# EspressoCircuitry.net
KiCad netlist of a schematic drawn in EAGLE
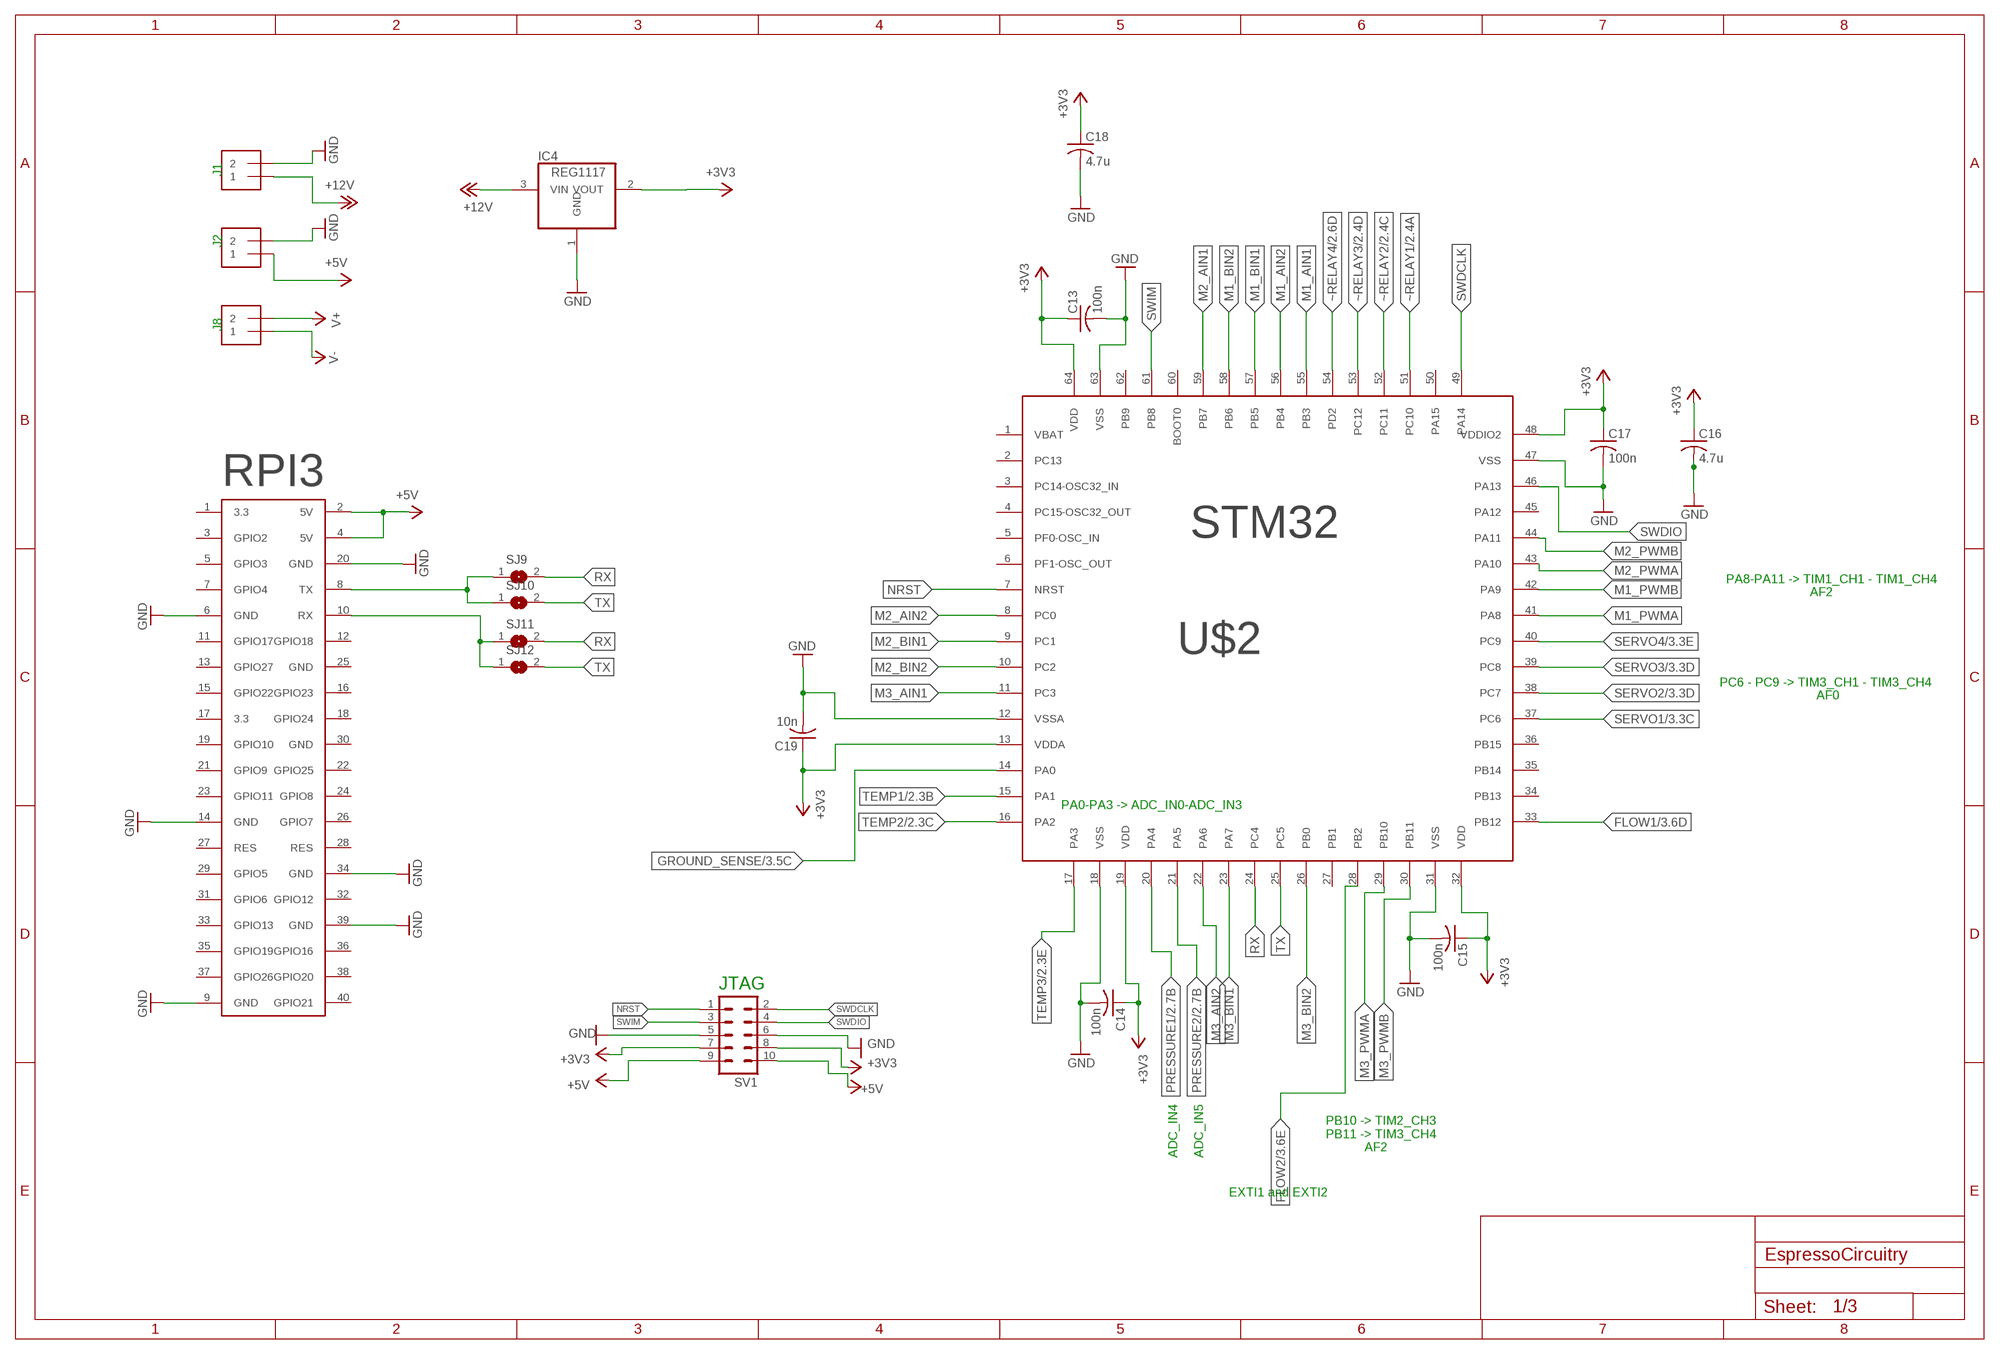
[diagram p0: schematic, sheet 1]
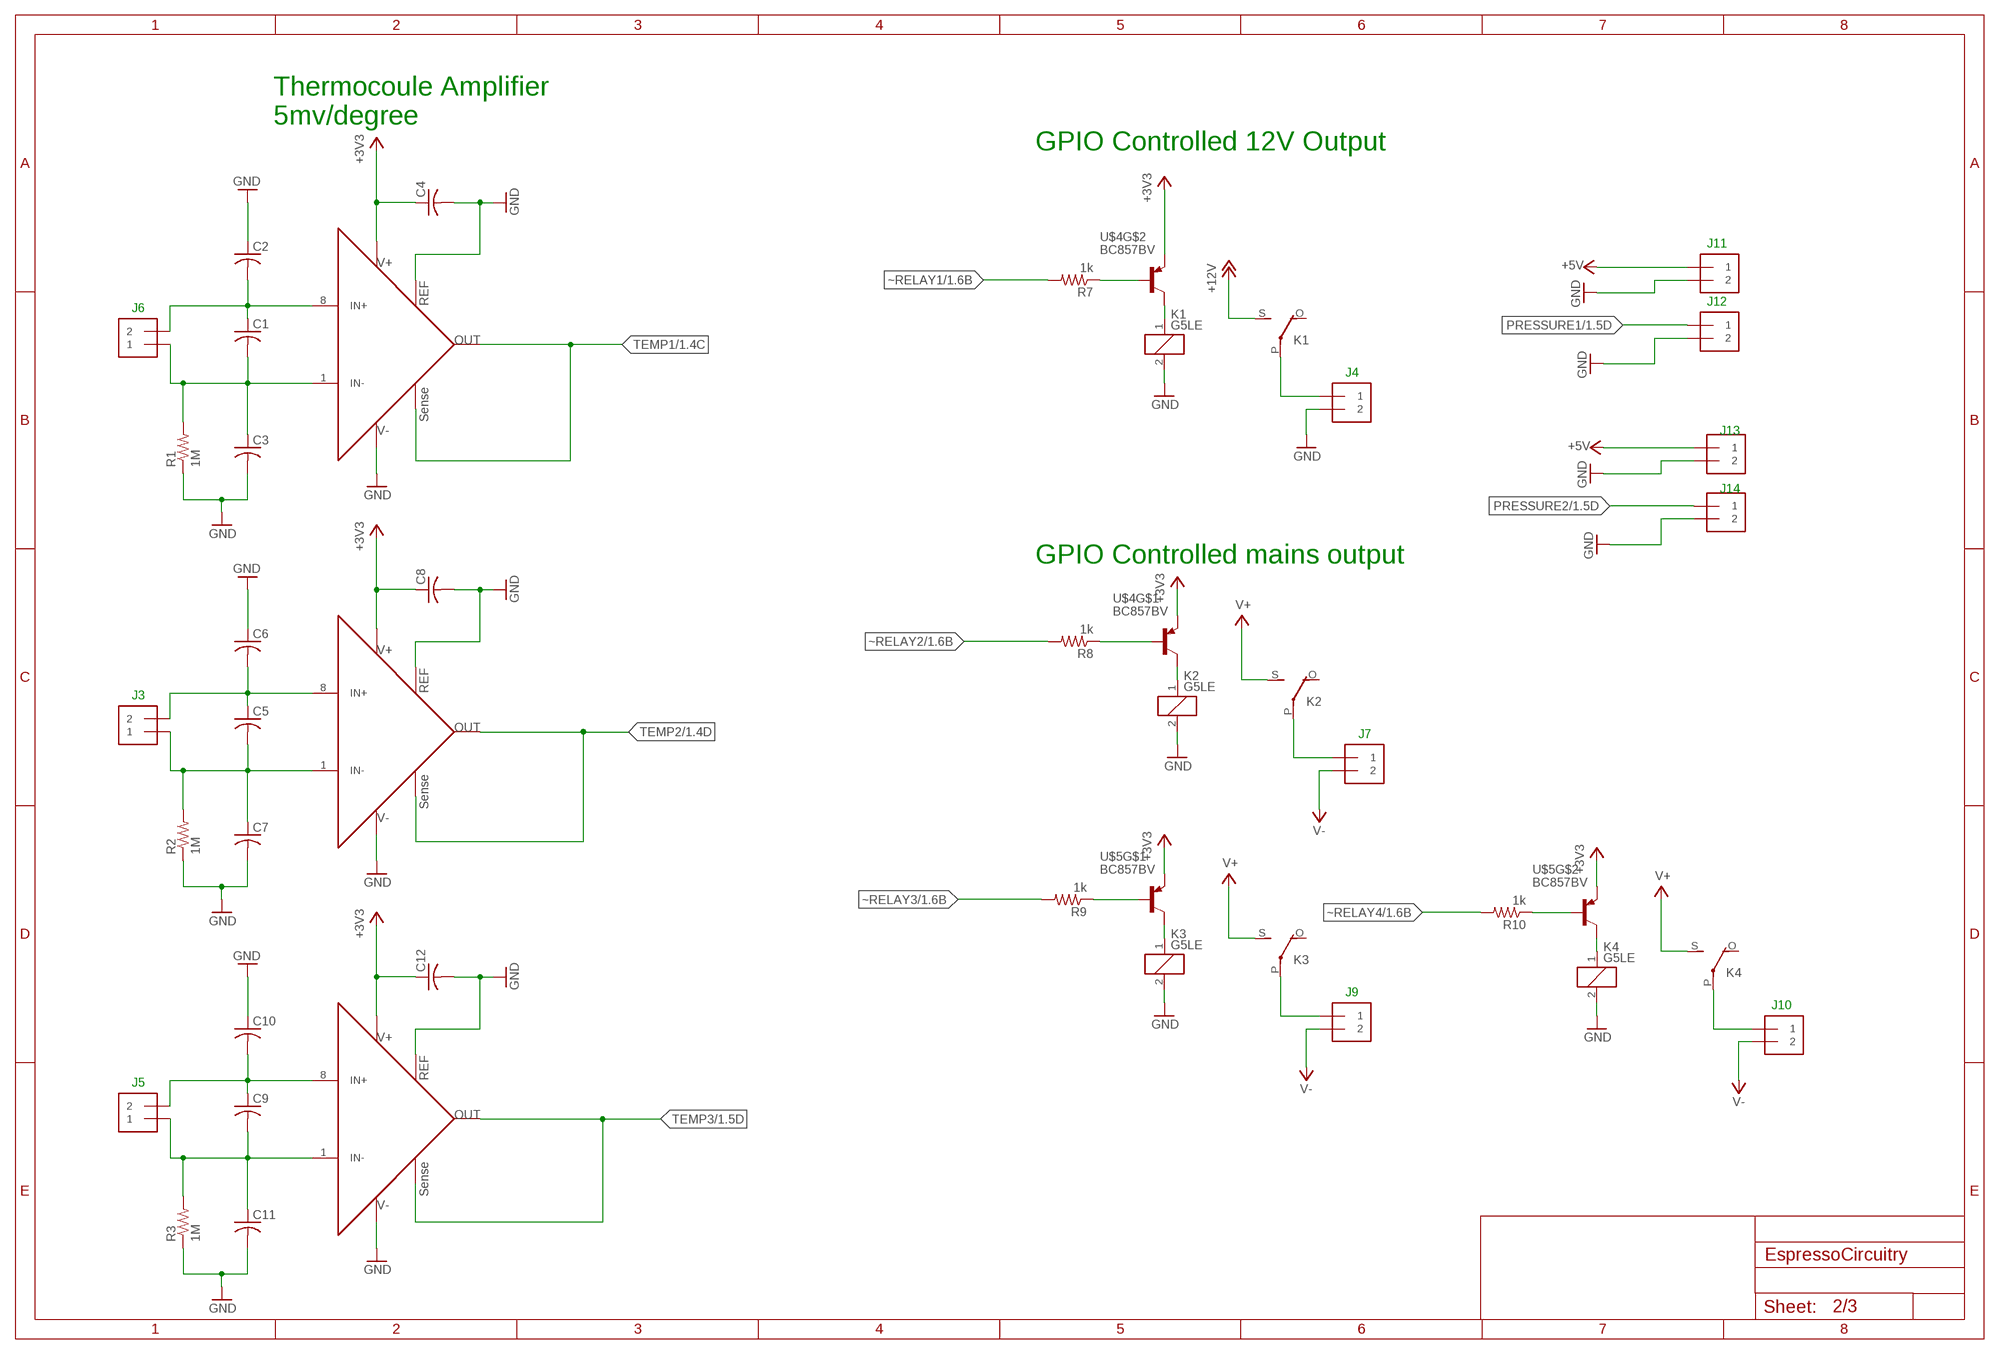
[diagram p1: schematic, sheet 2]
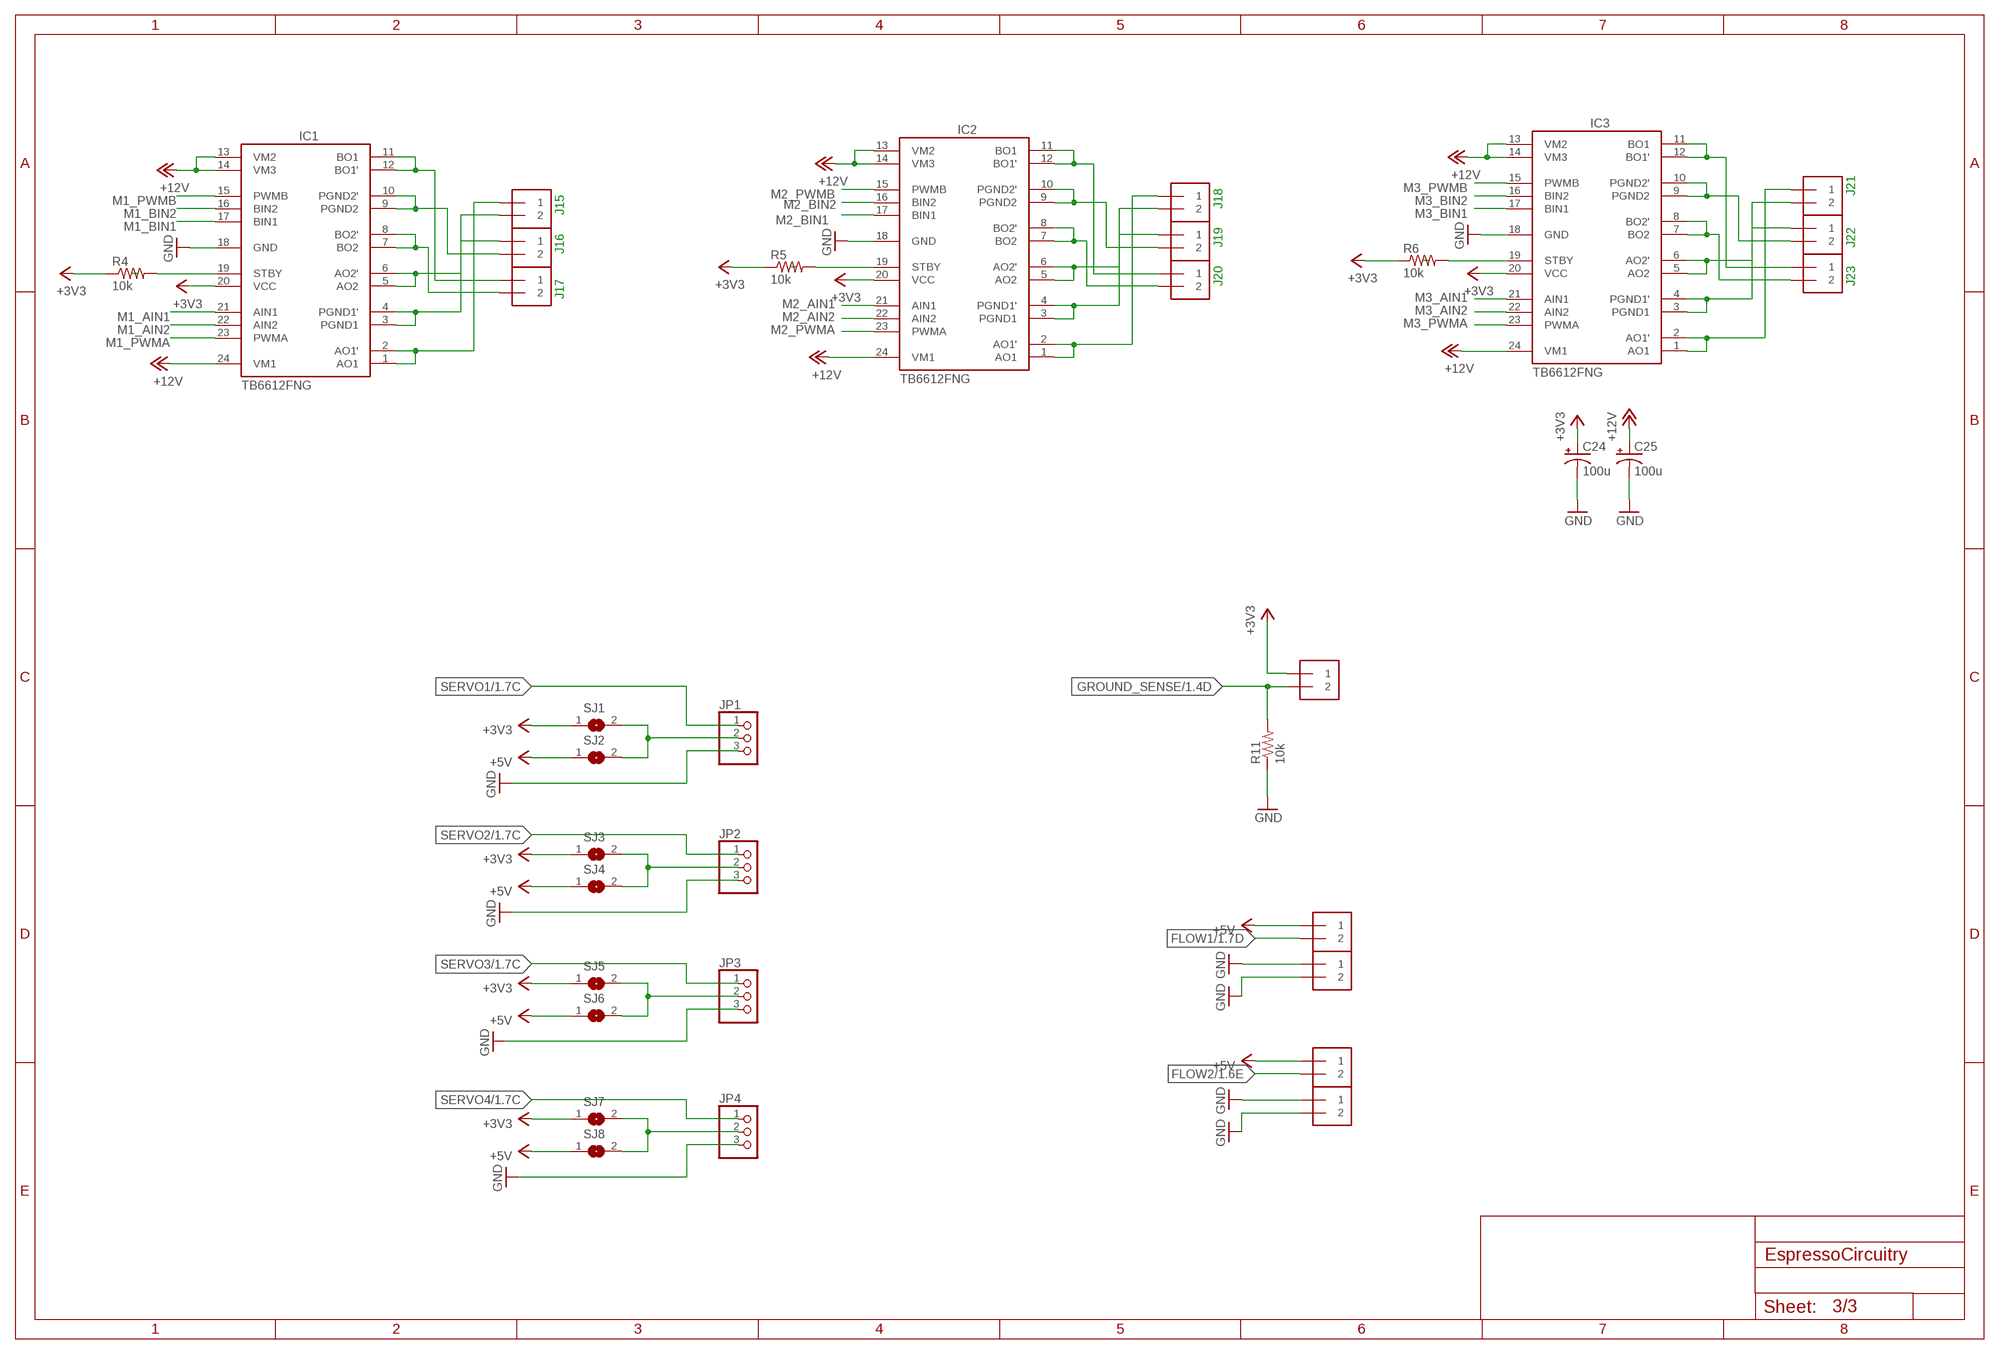
[diagram p2: schematic, sheet 3]

(export (version "E")
  (design (tool "Eeschema 10.0.6"))
  (components
    (comp (ref "C1")
      (value "C-USC0603")
      (footprint "eagle-import:C0603")
      (libsource (lib "eagle-import") (part "C-USC0603"))
    )
    (comp (ref "C2")
      (value "C-USC0603")
      (footprint "eagle-import:C0603")
      (libsource (lib "eagle-import") (part "C-USC0603"))
    )
    (comp (ref "C3")
      (value "C-USC0603")
      (footprint "eagle-import:C0603")
      (libsource (lib "eagle-import") (part "C-USC0603"))
    )
    (comp (ref "C4")
      (value "C-USC0603")
      (footprint "eagle-import:C0603")
      (libsource (lib "eagle-import") (part "C-USC0603"))
    )
    (comp (ref "C5")
      (value "C-USC0603")
      (footprint "eagle-import:C0603")
      (libsource (lib "eagle-import") (part "C-USC0603"))
    )
    (comp (ref "C6")
      (value "C-USC0603")
      (footprint "eagle-import:C0603")
      (libsource (lib "eagle-import") (part "C-USC0603"))
    )
    (comp (ref "C7")
      (value "C-USC0603")
      (footprint "eagle-import:C0603")
      (libsource (lib "eagle-import") (part "C-USC0603"))
    )
    (comp (ref "C8")
      (value "C-USC0603")
      (footprint "eagle-import:C0603")
      (libsource (lib "eagle-import") (part "C-USC0603"))
    )
    (comp (ref "C9")
      (value "C-USC0603")
      (footprint "eagle-import:C0603")
      (libsource (lib "eagle-import") (part "C-USC0603"))
    )
    (comp (ref "C10")
      (value "C-USC0603")
      (footprint "eagle-import:C0603")
      (libsource (lib "eagle-import") (part "C-USC0603"))
    )
    (comp (ref "C11")
      (value "C-USC0603")
      (footprint "eagle-import:C0603")
      (libsource (lib "eagle-import") (part "C-USC0603"))
    )
    (comp (ref "C12")
      (value "C-USC0603")
      (footprint "eagle-import:C0603")
      (libsource (lib "eagle-import") (part "C-USC0603"))
    )
    (comp (ref "J3")
      (value "1X2-3.5MM")
      (footprint "eagle-import:1X2-3.5MM")
      (libsource (lib "eagle-import") (part "1X2-3.5MM"))
    )
    (comp (ref "J4")
      (value "1X2-3.5MM")
      (footprint "eagle-import:1X2-3.5MM")
      (libsource (lib "eagle-import") (part "1X2-3.5MM"))
    )
    (comp (ref "J5")
      (value "1X2-3.5MM")
      (footprint "eagle-import:1X2-3.5MM")
      (libsource (lib "eagle-import") (part "1X2-3.5MM"))
    )
    (comp (ref "J6")
      (value "1X2-3.5MM")
      (footprint "eagle-import:1X2-3.5MM")
      (libsource (lib "eagle-import") (part "1X2-3.5MM"))
    )
    (comp (ref "J7")
      (value "1X2-3.5MM")
      (footprint "eagle-import:1X2-3.5MM")
      (libsource (lib "eagle-import") (part "1X2-3.5MM"))
    )
    (comp (ref "J9")
      (value "1X2-3.5MM")
      (footprint "eagle-import:1X2-3.5MM")
      (libsource (lib "eagle-import") (part "1X2-3.5MM"))
    )
    (comp (ref "J10")
      (value "1X2-3.5MM")
      (footprint "eagle-import:1X2-3.5MM")
      (libsource (lib "eagle-import") (part "1X2-3.5MM"))
    )
    (comp (ref "J11")
      (value "1X2-3.5MM")
      (footprint "eagle-import:1X2-3.5MM")
      (libsource (lib "eagle-import") (part "1X2-3.5MM"))
    )
    (comp (ref "J12")
      (value "1X2-3.5MM")
      (footprint "eagle-import:1X2-3.5MM")
      (libsource (lib "eagle-import") (part "1X2-3.5MM"))
    )
    (comp (ref "J13")
      (value "1X2-3.5MM")
      (footprint "eagle-import:1X2-3.5MM")
      (libsource (lib "eagle-import") (part "1X2-3.5MM"))
    )
    (comp (ref "J14")
      (value "1X2-3.5MM")
      (footprint "eagle-import:1X2-3.5MM")
      (libsource (lib "eagle-import") (part "1X2-3.5MM"))
    )
    (comp (ref "K1")
      (value "G5LE")
      (footprint "eagle-import:G5LE")
      (libsource (lib "eagle-import") (part "G5LE"))
    )
    (comp (ref "K2")
      (value "G5LE")
      (footprint "eagle-import:G5LE")
      (libsource (lib "eagle-import") (part "G5LE"))
    )
    (comp (ref "K3")
      (value "G5LE")
      (footprint "eagle-import:G5LE")
      (libsource (lib "eagle-import") (part "G5LE"))
    )
    (comp (ref "K4")
      (value "G5LE")
      (footprint "eagle-import:G5LE")
      (libsource (lib "eagle-import") (part "G5LE"))
    )
    (comp (ref "R1")
      (value "1M")
      (footprint "eagle-import:R0603")
      (libsource (lib "eagle-import") (part "R-US_R0603"))
    )
    (comp (ref "R2")
      (value "1M")
      (footprint "eagle-import:R0603")
      (libsource (lib "eagle-import") (part "R-US_R0603"))
    )
    (comp (ref "R3")
      (value "1M")
      (footprint "eagle-import:R0603")
      (libsource (lib "eagle-import") (part "R-US_R0603"))
    )
    (comp (ref "R7")
      (value "1k")
      (footprint "eagle-import:R0603")
      (libsource (lib "eagle-import") (part "R-US_R0603"))
    )
    (comp (ref "R8")
      (value "1k")
      (footprint "eagle-import:R0603")
      (libsource (lib "eagle-import") (part "R-US_R0603"))
    )
    (comp (ref "R9")
      (value "1k")
      (footprint "eagle-import:R0603")
      (libsource (lib "eagle-import") (part "R-US_R0603"))
    )
    (comp (ref "R10")
      (value "1k")
      (footprint "eagle-import:R0603")
      (libsource (lib "eagle-import") (part "R-US_R0603"))
    )
    (comp (ref "U$3")
      (value "AD8494")
      (footprint "eagle-import:TSSOP8")
      (libsource (lib "eagle-import") (part "AD8494"))
    )
    (comp (ref "U$4")
      (value "BC857BV")
      (footprint "eagle-import:SOT-563")
      (libsource (lib "eagle-import") (part "BC857BV"))
    )
    (comp (ref "U$5")
      (value "BC857BV")
      (footprint "eagle-import:SOT-563")
      (libsource (lib "eagle-import") (part "BC857BV"))
    )
    (comp (ref "U$6")
      (value "AD8494")
      (footprint "eagle-import:TSSOP8")
      (libsource (lib "eagle-import") (part "AD8494"))
    )
    (comp (ref "U$7")
      (value "AD8494")
      (footprint "eagle-import:TSSOP8")
      (libsource (lib "eagle-import") (part "AD8494"))
    )
    (comp (ref "C13")
      (value "100n")
      (footprint "eagle-import:C0603")
      (libsource (lib "eagle-import") (part "C-USC0603"))
    )
    (comp (ref "C14")
      (value "100n")
      (footprint "eagle-import:C0603")
      (libsource (lib "eagle-import") (part "C-USC0603"))
    )
    (comp (ref "C15")
      (value "100n")
      (footprint "eagle-import:C0603")
      (libsource (lib "eagle-import") (part "C-USC0603"))
    )
    (comp (ref "C16")
      (value "4.7u")
      (footprint "eagle-import:C0603")
      (libsource (lib "eagle-import") (part "C-USC0603"))
    )
    (comp (ref "C17")
      (value "100n")
      (footprint "eagle-import:C0603")
      (libsource (lib "eagle-import") (part "C-USC0603"))
    )
    (comp (ref "C18")
      (value "4.7u")
      (footprint "eagle-import:C0603")
      (libsource (lib "eagle-import") (part "C-USC0603"))
    )
    (comp (ref "C19")
      (value "10n")
      (footprint "eagle-import:C0603")
      (libsource (lib "eagle-import") (part "C-USC0603"))
    )
    (comp (ref "IC4")
      (value "REG1117")
      (footprint "eagle-import:SOT223")
      (libsource (lib "eagle-import") (part "REG1117"))
    )
    (comp (ref "J1")
      (value "1X2-3.5MM")
      (footprint "eagle-import:1X2-3.5MM")
      (libsource (lib "eagle-import") (part "1X2-3.5MM"))
    )
    (comp (ref "J2")
      (value "1X2-3.5MM")
      (footprint "eagle-import:1X2-3.5MM")
      (libsource (lib "eagle-import") (part "1X2-3.5MM"))
    )
    (comp (ref "J8")
      (value "1X2-3.5MM")
      (footprint "eagle-import:1X2-3.5MM")
      (libsource (lib "eagle-import") (part "1X2-3.5MM"))
    )
    (comp (ref "SJ9") (value "SJ") (footprint "eagle-import:SJ") (libsource (lib "eagle-import") (part "SJ")))
    (comp (ref "SJ10")
      (value "SJ")
      (footprint "eagle-import:SJ")
      (libsource (lib "eagle-import") (part "SJ"))
    )
    (comp (ref "SJ11")
      (value "SJ")
      (footprint "eagle-import:SJ")
      (libsource (lib "eagle-import") (part "SJ"))
    )
    (comp (ref "SJ12")
      (value "SJ")
      (footprint "eagle-import:SJ")
      (libsource (lib "eagle-import") (part "SJ"))
    )
    (comp (ref "SV1")
      (value "MA05-2")
      (footprint "eagle-import:MA05-2")
      (libsource (lib "eagle-import") (part "MA05-2"))
    )
    (comp (ref "U$1")
      (value "RPI")
      (footprint "eagle-import:FE20-2")
      (libsource (lib "eagle-import") (part "RPI"))
    )
    (comp (ref "U$2")
      (value "STM32F072RBT6LGFP64")
      (footprint "eagle-import:PLQFP64-1")
      (libsource (lib "eagle-import") (part "STM32F072RBT6LGFP64"))
    )
    (comp (ref "C24")
      (value "100u")
      (footprint "eagle-import:E2,5-5")
      (libsource (lib "eagle-import") (part "CPOL-USE2.5-5"))
    )
    (comp (ref "C25")
      (value "100u")
      (footprint "eagle-import:E2,5-5")
      (libsource (lib "eagle-import") (part "CPOL-USE2.5-5"))
    )
    (comp (ref "IC1")
      (value "TB6612FNG")
      (footprint "eagle-import:SSOP24")
      (libsource (lib "eagle-import") (part "TB6612FNG"))
    )
    (comp (ref "IC2")
      (value "TB6612FNG")
      (footprint "eagle-import:SSOP24")
      (libsource (lib "eagle-import") (part "TB6612FNG"))
    )
    (comp (ref "IC3")
      (value "TB6612FNG")
      (footprint "eagle-import:SSOP24")
      (libsource (lib "eagle-import") (part "TB6612FNG"))
    )
    (comp (ref "J15")
      (value "1X2-3.5MM")
      (footprint "eagle-import:1X2-3.5MM")
      (libsource (lib "eagle-import") (part "1X2-3.5MM"))
    )
    (comp (ref "J16")
      (value "1X2-3.5MM")
      (footprint "eagle-import:1X2-3.5MM")
      (libsource (lib "eagle-import") (part "1X2-3.5MM"))
    )
    (comp (ref "J17")
      (value "1X2-3.5MM")
      (footprint "eagle-import:1X2-3.5MM")
      (libsource (lib "eagle-import") (part "1X2-3.5MM"))
    )
    (comp (ref "J18")
      (value "1X2-3.5MM")
      (footprint "eagle-import:1X2-3.5MM")
      (libsource (lib "eagle-import") (part "1X2-3.5MM"))
    )
    (comp (ref "J19")
      (value "1X2-3.5MM")
      (footprint "eagle-import:1X2-3.5MM")
      (libsource (lib "eagle-import") (part "1X2-3.5MM"))
    )
    (comp (ref "J20")
      (value "1X2-3.5MM")
      (footprint "eagle-import:1X2-3.5MM")
      (libsource (lib "eagle-import") (part "1X2-3.5MM"))
    )
    (comp (ref "J21")
      (value "1X2-3.5MM")
      (footprint "eagle-import:1X2-3.5MM")
      (libsource (lib "eagle-import") (part "1X2-3.5MM"))
    )
    (comp (ref "J22")
      (value "1X2-3.5MM")
      (footprint "eagle-import:1X2-3.5MM")
      (libsource (lib "eagle-import") (part "1X2-3.5MM"))
    )
    (comp (ref "J23")
      (value "1X2-3.5MM")
      (footprint "eagle-import:1X2-3.5MM")
      (libsource (lib "eagle-import") (part "1X2-3.5MM"))
    )
    (comp (ref "J24")
      (value "1X2-3.5MM")
      (footprint "eagle-import:1X2-3.5MM")
      (libsource (lib "eagle-import") (part "1X2-3.5MM"))
    )
    (comp (ref "J25")
      (value "1X2-3.5MM")
      (footprint "eagle-import:1X2-3.5MM")
      (libsource (lib "eagle-import") (part "1X2-3.5MM"))
    )
    (comp (ref "J26")
      (value "1X2-3.5MM")
      (footprint "eagle-import:1X2-3.5MM")
      (libsource (lib "eagle-import") (part "1X2-3.5MM"))
    )
    (comp (ref "J27")
      (value "1X2-3.5MM")
      (footprint "eagle-import:1X2-3.5MM")
      (libsource (lib "eagle-import") (part "1X2-3.5MM"))
    )
    (comp (ref "J28")
      (value "1X2-3.5MM")
      (footprint "eagle-import:1X2-3.5MM")
      (libsource (lib "eagle-import") (part "1X2-3.5MM"))
    )
    (comp (ref "JP1")
      (value "PINHD-1X3")
      (footprint "eagle-import:1X03")
      (libsource (lib "eagle-import") (part "PINHD-1X3"))
    )
    (comp (ref "JP2")
      (value "PINHD-1X3")
      (footprint "eagle-import:1X03")
      (libsource (lib "eagle-import") (part "PINHD-1X3"))
    )
    (comp (ref "JP3")
      (value "PINHD-1X3")
      (footprint "eagle-import:1X03")
      (libsource (lib "eagle-import") (part "PINHD-1X3"))
    )
    (comp (ref "JP4")
      (value "PINHD-1X3")
      (footprint "eagle-import:1X03")
      (libsource (lib "eagle-import") (part "PINHD-1X3"))
    )
    (comp (ref "R4")
      (value "10k")
      (footprint "eagle-import:R0603")
      (libsource (lib "eagle-import") (part "R-US_R0603"))
    )
    (comp (ref "R5")
      (value "10k")
      (footprint "eagle-import:R0603")
      (libsource (lib "eagle-import") (part "R-US_R0603"))
    )
    (comp (ref "R6")
      (value "10k")
      (footprint "eagle-import:R0603")
      (libsource (lib "eagle-import") (part "R-US_R0603"))
    )
    (comp (ref "R11")
      (value "10k")
      (footprint "eagle-import:R0603")
      (libsource (lib "eagle-import") (part "R-US_R0603"))
    )
    (comp (ref "SJ1") (value "SJ") (footprint "eagle-import:SJ") (libsource (lib "eagle-import") (part "SJ")))
    (comp (ref "SJ2") (value "SJ") (footprint "eagle-import:SJ") (libsource (lib "eagle-import") (part "SJ")))
    (comp (ref "SJ3") (value "SJ") (footprint "eagle-import:SJ") (libsource (lib "eagle-import") (part "SJ")))
    (comp (ref "SJ4") (value "SJ") (footprint "eagle-import:SJ") (libsource (lib "eagle-import") (part "SJ")))
    (comp (ref "SJ5") (value "SJ") (footprint "eagle-import:SJ") (libsource (lib "eagle-import") (part "SJ")))
    (comp (ref "SJ6") (value "SJ") (footprint "eagle-import:SJ") (libsource (lib "eagle-import") (part "SJ")))
    (comp (ref "SJ7") (value "SJ") (footprint "eagle-import:SJ") (libsource (lib "eagle-import") (part "SJ")))
    (comp (ref "SJ8") (value "SJ") (footprint "eagle-import:SJ") (libsource (lib "eagle-import") (part "SJ")))
  )
  (nets
    (net (code "1") (name "+3V3") (class "Default")
      (node (ref "C12") (pin "1") (pinfunction "1_1") (pintype "passive"))
      (node (ref "C13") (pin "1") (pinfunction "1_1") (pintype "passive"))
      (node (ref "C14") (pin "1") (pinfunction "1_1") (pintype "passive"))
      (node (ref "C15") (pin "1") (pinfunction "1_1") (pintype "passive"))
      (node (ref "C16") (pin "1") (pinfunction "1_1") (pintype "passive"))
      (node (ref "C17") (pin "1") (pinfunction "1_1") (pintype "passive"))
      (node (ref "C18") (pin "1") (pinfunction "1_1") (pintype "passive"))
      (node (ref "C19") (pin "1") (pinfunction "1_1") (pintype "passive"))
      (node (ref "C24") (pin "+") (pinfunction "+_+") (pintype "passive"))
      (node (ref "C4") (pin "1") (pinfunction "1_1") (pintype "passive"))
      (node (ref "C8") (pin "1") (pinfunction "1_1") (pintype "passive"))
      (node (ref "IC1") (pin "20") (pinfunction "VCC_20") (pintype "power_in"))
      (node (ref "IC2") (pin "20") (pinfunction "VCC_20") (pintype "power_in"))
      (node (ref "IC3") (pin "20") (pinfunction "VCC_20") (pintype "power_in"))
      (node (ref "IC4") (pin "2") (pinfunction "VOUT_2") (pintype "output"))
      (node (ref "J24") (pin "1") (pinfunction "1_1") (pintype "passive"))
      (node (ref "R4") (pin "1") (pinfunction "1_1") (pintype "passive"))
      (node (ref "R5") (pin "1") (pinfunction "1_1") (pintype "passive"))
      (node (ref "R6") (pin "1") (pinfunction "1_1") (pintype "passive"))
      (node (ref "SJ1") (pin "1") (pinfunction "1_1") (pintype "passive"))
      (node (ref "SJ3") (pin "1") (pinfunction "1_1") (pintype "passive"))
      (node (ref "SJ5") (pin "1") (pinfunction "1_1") (pintype "passive"))
      (node (ref "SJ7") (pin "1") (pinfunction "1_1") (pintype "passive"))
      (node (ref "SV1") (pin "7") (pinfunction "7_7") (pintype "passive"))
      (node (ref "SV1") (pin "8") (pinfunction "8_8") (pintype "passive"))
      (node (ref "U$2") (pin "13") (pinfunction "VDDA_13") (pintype "bidirectional"))
      (node (ref "U$2") (pin "19") (pinfunction "VDD_19") (pintype "bidirectional"))
      (node (ref "U$2") (pin "32") (pinfunction "VDD_32") (pintype "bidirectional"))
      (node (ref "U$2") (pin "48") (pinfunction "VDDIO2_48") (pintype "bidirectional"))
      (node (ref "U$2") (pin "64") (pinfunction "VDD_64") (pintype "bidirectional"))
      (node (ref "U$3") (pin "7") (pinfunction "V+_7") (pintype "bidirectional"))
      (node (ref "U$4") (pin "P$3") (pinfunction "E_P$3") (pintype "passive"))
      (node (ref "U$4") (pin "P$6") (pinfunction "E_P$6") (pintype "passive"))
      (node (ref "U$5") (pin "P$3") (pinfunction "E_P$3") (pintype "passive"))
      (node (ref "U$5") (pin "P$6") (pinfunction "E_P$6") (pintype "passive"))
      (node (ref "U$6") (pin "7") (pinfunction "V+_7") (pintype "bidirectional"))
      (node (ref "U$7") (pin "7") (pinfunction "V+_7") (pintype "bidirectional"))
    )
    (net (code "2") (name "+5V") (class "Default")
      (node (ref "J11") (pin "1") (pinfunction "1_1") (pintype "passive"))
      (node (ref "J13") (pin "1") (pinfunction "1_1") (pintype "passive"))
      (node (ref "J2") (pin "1") (pinfunction "1_1") (pintype "passive"))
      (node (ref "J25") (pin "1") (pinfunction "1_1") (pintype "passive"))
      (node (ref "J27") (pin "1") (pinfunction "1_1") (pintype "passive"))
      (node (ref "SJ2") (pin "1") (pinfunction "1_1") (pintype "passive"))
      (node (ref "SJ4") (pin "1") (pinfunction "1_1") (pintype "passive"))
      (node (ref "SJ6") (pin "1") (pinfunction "1_1") (pintype "passive"))
      (node (ref "SJ8") (pin "1") (pinfunction "1_1") (pintype "passive"))
      (node (ref "SV1") (pin "10") (pinfunction "10_10") (pintype "passive"))
      (node (ref "SV1") (pin "9") (pinfunction "9_9") (pintype "passive"))
      (node (ref "U$1") (pin "2") (pinfunction "5V_2") (pintype "bidirectional"))
      (node (ref "U$1") (pin "4") (pinfunction "5V_4") (pintype "bidirectional"))
    )
    (net (code "3") (name "+12V") (class "Default")
      (node (ref "C25") (pin "+") (pinfunction "+_+") (pintype "passive"))
      (node (ref "IC1") (pin "13") (pinfunction "VM2_13") (pintype "power_in"))
      (node (ref "IC1") (pin "14") (pinfunction "VM3_14") (pintype "power_in"))
      (node (ref "IC1") (pin "24") (pinfunction "VM1_24") (pintype "power_in"))
      (node (ref "IC2") (pin "13") (pinfunction "VM2_13") (pintype "power_in"))
      (node (ref "IC2") (pin "14") (pinfunction "VM3_14") (pintype "power_in"))
      (node (ref "IC2") (pin "24") (pinfunction "VM1_24") (pintype "power_in"))
      (node (ref "IC3") (pin "13") (pinfunction "VM2_13") (pintype "power_in"))
      (node (ref "IC3") (pin "14") (pinfunction "VM3_14") (pintype "power_in"))
      (node (ref "IC3") (pin "24") (pinfunction "VM1_24") (pintype "power_in"))
      (node (ref "IC4") (pin "3") (pinfunction "VIN_3") (pintype "input"))
      (node (ref "J1") (pin "1") (pinfunction "1_1") (pintype "passive"))
      (node (ref "K1") (pin "S") (pinfunction "S_S") (pintype "passive"))
    )
    (net (code "4") (name "FLOW1") (class "Default")
      (node (ref "J25") (pin "2") (pinfunction "2_2") (pintype "passive"))
      (node (ref "U$2") (pin "33") (pinfunction "PB12_33") (pintype "bidirectional"))
    )
    (net (code "5") (name "FLOW2") (class "Default")
      (node (ref "J27") (pin "2") (pinfunction "2_2") (pintype "passive"))
      (node (ref "U$2") (pin "28") (pinfunction "PB2_28") (pintype "bidirectional"))
    )
    (net (code "6") (name "GND") (class "Default")
      (node (ref "C10") (pin "1") (pinfunction "1_1") (pintype "passive"))
      (node (ref "C11") (pin "2") (pinfunction "2_2") (pintype "passive"))
      (node (ref "C12") (pin "2") (pinfunction "2_2") (pintype "passive"))
      (node (ref "C13") (pin "2") (pinfunction "2_2") (pintype "passive"))
      (node (ref "C14") (pin "2") (pinfunction "2_2") (pintype "passive"))
      (node (ref "C15") (pin "2") (pinfunction "2_2") (pintype "passive"))
      (node (ref "C16") (pin "2") (pinfunction "2_2") (pintype "passive"))
      (node (ref "C17") (pin "2") (pinfunction "2_2") (pintype "passive"))
      (node (ref "C18") (pin "2") (pinfunction "2_2") (pintype "passive"))
      (node (ref "C19") (pin "2") (pinfunction "2_2") (pintype "passive"))
      (node (ref "C2") (pin "1") (pinfunction "1_1") (pintype "passive"))
      (node (ref "C24") (pin "-") (pinfunction "-_-") (pintype "passive"))
      (node (ref "C25") (pin "-") (pinfunction "-_-") (pintype "passive"))
      (node (ref "C3") (pin "2") (pinfunction "2_2") (pintype "passive"))
      (node (ref "C4") (pin "2") (pinfunction "2_2") (pintype "passive"))
      (node (ref "C6") (pin "1") (pinfunction "1_1") (pintype "passive"))
      (node (ref "C7") (pin "2") (pinfunction "2_2") (pintype "passive"))
      (node (ref "C8") (pin "2") (pinfunction "2_2") (pintype "passive"))
      (node (ref "IC1") (pin "18") (pinfunction "GND_18") (pintype "power_in"))
      (node (ref "IC2") (pin "18") (pinfunction "GND_18") (pintype "power_in"))
      (node (ref "IC3") (pin "18") (pinfunction "GND_18") (pintype "power_in"))
      (node (ref "IC4") (pin "1") (pinfunction "GND_1") (pintype "power_in"))
      (node (ref "J1") (pin "2") (pinfunction "2_2") (pintype "passive"))
      (node (ref "J11") (pin "2") (pinfunction "2_2") (pintype "passive"))
      (node (ref "J12") (pin "2") (pinfunction "2_2") (pintype "passive"))
      (node (ref "J13") (pin "2") (pinfunction "2_2") (pintype "passive"))
      (node (ref "J14") (pin "2") (pinfunction "2_2") (pintype "passive"))
      (node (ref "J2") (pin "2") (pinfunction "2_2") (pintype "passive"))
      (node (ref "J26") (pin "1") (pinfunction "1_1") (pintype "passive"))
      (node (ref "J26") (pin "2") (pinfunction "2_2") (pintype "passive"))
      (node (ref "J28") (pin "1") (pinfunction "1_1") (pintype "passive"))
      (node (ref "J28") (pin "2") (pinfunction "2_2") (pintype "passive"))
      (node (ref "J4") (pin "2") (pinfunction "2_2") (pintype "passive"))
      (node (ref "JP1") (pin "3") (pinfunction "3_3") (pintype "passive"))
      (node (ref "JP2") (pin "3") (pinfunction "3_3") (pintype "passive"))
      (node (ref "JP3") (pin "3") (pinfunction "3_3") (pintype "passive"))
      (node (ref "JP4") (pin "3") (pinfunction "3_3") (pintype "passive"))
      (node (ref "K1") (pin "2") (pinfunction "2_2") (pintype "passive"))
      (node (ref "K2") (pin "2") (pinfunction "2_2") (pintype "passive"))
      (node (ref "K3") (pin "2") (pinfunction "2_2") (pintype "passive"))
      (node (ref "K4") (pin "2") (pinfunction "2_2") (pintype "passive"))
      (node (ref "R1") (pin "1") (pinfunction "1_1") (pintype "passive"))
      (node (ref "R11") (pin "1") (pinfunction "1_1") (pintype "passive"))
      (node (ref "R2") (pin "1") (pinfunction "1_1") (pintype "passive"))
      (node (ref "R3") (pin "1") (pinfunction "1_1") (pintype "passive"))
      (node (ref "SV1") (pin "5") (pinfunction "5_5") (pintype "passive"))
      (node (ref "SV1") (pin "6") (pinfunction "6_6") (pintype "passive"))
      (node (ref "U$1") (pin "14") (pinfunction "GND_14") (pintype "bidirectional"))
      (node (ref "U$1") (pin "20") (pinfunction "GND_20") (pintype "bidirectional"))
      (node (ref "U$1") (pin "34") (pinfunction "GND_34") (pintype "bidirectional"))
      (node (ref "U$1") (pin "39") (pinfunction "GND_39") (pintype "bidirectional"))
      (node (ref "U$1") (pin "6") (pinfunction "GND_6") (pintype "bidirectional"))
      (node (ref "U$1") (pin "9") (pinfunction "GND_9") (pintype "bidirectional"))
      (node (ref "U$2") (pin "12") (pinfunction "VSSA_12") (pintype "bidirectional"))
      (node (ref "U$2") (pin "18") (pinfunction "VSS_18") (pintype "bidirectional"))
      (node (ref "U$2") (pin "31") (pinfunction "VSS_31") (pintype "bidirectional"))
      (node (ref "U$2") (pin "47") (pinfunction "VSS_47") (pintype "bidirectional"))
      (node (ref "U$2") (pin "63") (pinfunction "VSS_63") (pintype "bidirectional"))
      (node (ref "U$3") (pin "2") (pinfunction "REF_2") (pintype "bidirectional"))
      (node (ref "U$3") (pin "3") (pinfunction "V-_3") (pintype "bidirectional"))
      (node (ref "U$6") (pin "2") (pinfunction "REF_2") (pintype "bidirectional"))
      (node (ref "U$6") (pin "3") (pinfunction "V-_3") (pintype "bidirectional"))
      (node (ref "U$7") (pin "2") (pinfunction "REF_2") (pintype "bidirectional"))
      (node (ref "U$7") (pin "3") (pinfunction "V-_3") (pintype "bidirectional"))
    )
    (net (code "7") (name "GROUND_SENSE") (class "Default")
      (node (ref "J24") (pin "2") (pinfunction "2_2") (pintype "passive"))
      (node (ref "R11") (pin "2") (pinfunction "2_2") (pintype "passive"))
      (node (ref "U$2") (pin "14") (pinfunction "PA0_14") (pintype "bidirectional"))
    )
    (net (code "8") (name "M1_AIN1") (class "Default")
      (node (ref "IC1") (pin "21") (pinfunction "AIN1_21") (pintype "input"))
      (node (ref "U$2") (pin "55") (pinfunction "PB3_55") (pintype "bidirectional"))
    )
    (net (code "9") (name "M1_AIN2") (class "Default")
      (node (ref "IC1") (pin "22") (pinfunction "AIN2_22") (pintype "input"))
      (node (ref "U$2") (pin "56") (pinfunction "PB4_56") (pintype "bidirectional"))
    )
    (net (code "10") (name "M1_BIN1") (class "Default")
      (node (ref "IC1") (pin "17") (pinfunction "BIN1_17") (pintype "input"))
      (node (ref "U$2") (pin "57") (pinfunction "PB5_57") (pintype "bidirectional"))
    )
    (net (code "11") (name "M1_BIN2") (class "Default")
      (node (ref "IC1") (pin "16") (pinfunction "BIN2_16") (pintype "input"))
      (node (ref "U$2") (pin "58") (pinfunction "PB6_58") (pintype "bidirectional"))
    )
    (net (code "12") (name "M1_PWMA") (class "Default")
      (node (ref "IC1") (pin "23") (pinfunction "PWMA_23") (pintype "input"))
      (node (ref "U$2") (pin "41") (pinfunction "PA8_41") (pintype "bidirectional"))
    )
    (net (code "13") (name "M1_PWMB") (class "Default")
      (node (ref "IC1") (pin "15") (pinfunction "PWMB_15") (pintype "input"))
      (node (ref "U$2") (pin "42") (pinfunction "PA9_42") (pintype "bidirectional"))
    )
    (net (code "14") (name "M2_AIN1") (class "Default")
      (node (ref "IC2") (pin "21") (pinfunction "AIN1_21") (pintype "input"))
      (node (ref "U$2") (pin "59") (pinfunction "PB7_59") (pintype "bidirectional"))
    )
    (net (code "15") (name "M2_AIN2") (class "Default")
      (node (ref "IC2") (pin "22") (pinfunction "AIN2_22") (pintype "input"))
      (node (ref "U$2") (pin "8") (pinfunction "PC0_8") (pintype "bidirectional"))
    )
    (net (code "16") (name "M2_BIN1") (class "Default")
      (node (ref "IC2") (pin "17") (pinfunction "BIN1_17") (pintype "input"))
      (node (ref "U$2") (pin "9") (pinfunction "PC1_9") (pintype "bidirectional"))
    )
    (net (code "17") (name "M2_BIN2") (class "Default")
      (node (ref "IC2") (pin "16") (pinfunction "BIN2_16") (pintype "input"))
      (node (ref "U$2") (pin "10") (pinfunction "PC2_10") (pintype "bidirectional"))
    )
    (net (code "18") (name "M2_PWMA") (class "Default")
      (node (ref "IC2") (pin "23") (pinfunction "PWMA_23") (pintype "input"))
      (node (ref "U$2") (pin "43") (pinfunction "PA10_43") (pintype "bidirectional"))
    )
    (net (code "19") (name "M2_PWMB") (class "Default")
      (node (ref "IC2") (pin "15") (pinfunction "PWMB_15") (pintype "input"))
      (node (ref "U$2") (pin "44") (pinfunction "PA11_44") (pintype "bidirectional"))
    )
    (net (code "20") (name "M3_AIN1") (class "Default")
      (node (ref "IC3") (pin "21") (pinfunction "AIN1_21") (pintype "input"))
      (node (ref "U$2") (pin "11") (pinfunction "PC3_11") (pintype "bidirectional"))
    )
    (net (code "21") (name "M3_AIN2") (class "Default")
      (node (ref "IC3") (pin "22") (pinfunction "AIN2_22") (pintype "input"))
      (node (ref "U$2") (pin "22") (pinfunction "PA6_22") (pintype "bidirectional"))
    )
    (net (code "22") (name "M3_BIN1") (class "Default")
      (node (ref "IC3") (pin "17") (pinfunction "BIN1_17") (pintype "input"))
      (node (ref "U$2") (pin "23") (pinfunction "PA7_23") (pintype "bidirectional"))
    )
    (net (code "23") (name "M3_BIN2") (class "Default")
      (node (ref "IC3") (pin "16") (pinfunction "BIN2_16") (pintype "input"))
      (node (ref "U$2") (pin "26") (pinfunction "PB0_26") (pintype "bidirectional"))
    )
    (net (code "24") (name "M3_PWMA") (class "Default")
      (node (ref "IC3") (pin "23") (pinfunction "PWMA_23") (pintype "input"))
      (node (ref "U$2") (pin "29") (pinfunction "PB10_29") (pintype "bidirectional"))
    )
    (net (code "25") (name "M3_PWMB") (class "Default")
      (node (ref "IC3") (pin "15") (pinfunction "PWMB_15") (pintype "input"))
      (node (ref "U$2") (pin "30") (pinfunction "PB11_30") (pintype "bidirectional"))
    )
    (net (code "26") (name "NRST") (class "Default")
      (node (ref "SV1") (pin "1") (pinfunction "1_1") (pintype "passive"))
      (node (ref "U$2") (pin "7") (pinfunction "NRST_7") (pintype "bidirectional"))
    )
    (net (code "27") (name "Net-(IC1-AO1')") (class "Default")
      (node (ref "IC1") (pin "1") (pinfunction "AO1_1") (pintype "output"))
      (node (ref "IC1") (pin "2") (pinfunction "AO1'_2") (pintype "output"))
      (node (ref "J15") (pin "1") (pinfunction "1_1") (pintype "passive"))
    )
    (net (code "28") (name "Net-(IC1-AO2')") (class "Default")
      (node (ref "IC1") (pin "5") (pinfunction "AO2_5") (pintype "output"))
      (node (ref "IC1") (pin "6") (pinfunction "AO2'_6") (pintype "output"))
      (node (ref "J15") (pin "2") (pinfunction "2_2") (pintype "passive"))
    )
    (net (code "29") (name "Net-(IC1-BO1')") (class "Default")
      (node (ref "IC1") (pin "11") (pinfunction "BO1_11") (pintype "output"))
      (node (ref "IC1") (pin "12") (pinfunction "BO1'_12") (pintype "output"))
      (node (ref "J17") (pin "1") (pinfunction "1_1") (pintype "passive"))
    )
    (net (code "30") (name "Net-(IC1-BO2')") (class "Default")
      (node (ref "IC1") (pin "7") (pinfunction "BO2_7") (pintype "output"))
      (node (ref "IC1") (pin "8") (pinfunction "BO2'_8") (pintype "output"))
      (node (ref "J17") (pin "2") (pinfunction "2_2") (pintype "passive"))
    )
    (net (code "31") (name "Net-(IC1-PGND1')") (class "Default")
      (node (ref "IC1") (pin "3") (pinfunction "PGND1_3") (pintype "power_in"))
      (node (ref "IC1") (pin "4") (pinfunction "PGND1'_4") (pintype "power_in"))
      (node (ref "J16") (pin "1") (pinfunction "1_1") (pintype "passive"))
    )
    (net (code "32") (name "Net-(IC1-PGND2')") (class "Default")
      (node (ref "IC1") (pin "10") (pinfunction "PGND2'_10") (pintype "power_in"))
      (node (ref "IC1") (pin "9") (pinfunction "PGND2_9") (pintype "power_in"))
      (node (ref "J16") (pin "2") (pinfunction "2_2") (pintype "passive"))
    )
    (net (code "33") (name "Net-(IC1-STBY)") (class "Default")
      (node (ref "IC1") (pin "19") (pinfunction "STBY_19") (pintype "input"))
      (node (ref "R4") (pin "2") (pinfunction "2_2") (pintype "passive"))
    )
    (net (code "34") (name "Net-(IC2-AO1')") (class "Default")
      (node (ref "IC2") (pin "1") (pinfunction "AO1_1") (pintype "output"))
      (node (ref "IC2") (pin "2") (pinfunction "AO1'_2") (pintype "output"))
      (node (ref "J18") (pin "1") (pinfunction "1_1") (pintype "passive"))
    )
    (net (code "35") (name "Net-(IC2-AO2')") (class "Default")
      (node (ref "IC2") (pin "5") (pinfunction "AO2_5") (pintype "output"))
      (node (ref "IC2") (pin "6") (pinfunction "AO2'_6") (pintype "output"))
      (node (ref "J18") (pin "2") (pinfunction "2_2") (pintype "passive"))
    )
    (net (code "36") (name "Net-(IC2-BO1')") (class "Default")
      (node (ref "IC2") (pin "11") (pinfunction "BO1_11") (pintype "output"))
      (node (ref "IC2") (pin "12") (pinfunction "BO1'_12") (pintype "output"))
      (node (ref "J20") (pin "1") (pinfunction "1_1") (pintype "passive"))
    )
    (net (code "37") (name "Net-(IC2-BO2')") (class "Default")
      (node (ref "IC2") (pin "7") (pinfunction "BO2_7") (pintype "output"))
      (node (ref "IC2") (pin "8") (pinfunction "BO2'_8") (pintype "output"))
      (node (ref "J20") (pin "2") (pinfunction "2_2") (pintype "passive"))
    )
    (net (code "38") (name "Net-(IC2-PGND1')") (class "Default")
      (node (ref "IC2") (pin "3") (pinfunction "PGND1_3") (pintype "power_in"))
      (node (ref "IC2") (pin "4") (pinfunction "PGND1'_4") (pintype "power_in"))
      (node (ref "J19") (pin "1") (pinfunction "1_1") (pintype "passive"))
    )
    (net (code "39") (name "Net-(IC2-PGND2')") (class "Default")
      (node (ref "IC2") (pin "10") (pinfunction "PGND2'_10") (pintype "power_in"))
      (node (ref "IC2") (pin "9") (pinfunction "PGND2_9") (pintype "power_in"))
      (node (ref "J19") (pin "2") (pinfunction "2_2") (pintype "passive"))
    )
    (net (code "40") (name "Net-(IC2-STBY)") (class "Default")
      (node (ref "IC2") (pin "19") (pinfunction "STBY_19") (pintype "input"))
      (node (ref "R5") (pin "2") (pinfunction "2_2") (pintype "passive"))
    )
    (net (code "41") (name "Net-(IC3-AO1')") (class "Default")
      (node (ref "IC3") (pin "1") (pinfunction "AO1_1") (pintype "output"))
      (node (ref "IC3") (pin "2") (pinfunction "AO1'_2") (pintype "output"))
      (node (ref "J21") (pin "1") (pinfunction "1_1") (pintype "passive"))
    )
    (net (code "42") (name "Net-(IC3-AO2')") (class "Default")
      (node (ref "IC3") (pin "5") (pinfunction "AO2_5") (pintype "output"))
      (node (ref "IC3") (pin "6") (pinfunction "AO2'_6") (pintype "output"))
      (node (ref "J21") (pin "2") (pinfunction "2_2") (pintype "passive"))
    )
    (net (code "43") (name "Net-(IC3-BO1')") (class "Default")
      (node (ref "IC3") (pin "11") (pinfunction "BO1_11") (pintype "output"))
      (node (ref "IC3") (pin "12") (pinfunction "BO1'_12") (pintype "output"))
      (node (ref "J23") (pin "1") (pinfunction "1_1") (pintype "passive"))
    )
    (net (code "44") (name "Net-(IC3-BO2')") (class "Default")
      (node (ref "IC3") (pin "7") (pinfunction "BO2_7") (pintype "output"))
      (node (ref "IC3") (pin "8") (pinfunction "BO2'_8") (pintype "output"))
      (node (ref "J23") (pin "2") (pinfunction "2_2") (pintype "passive"))
    )
    (net (code "45") (name "Net-(IC3-PGND1')") (class "Default")
      (node (ref "IC3") (pin "3") (pinfunction "PGND1_3") (pintype "power_in"))
      (node (ref "IC3") (pin "4") (pinfunction "PGND1'_4") (pintype "power_in"))
      (node (ref "J22") (pin "1") (pinfunction "1_1") (pintype "passive"))
    )
    (net (code "46") (name "Net-(IC3-PGND2')") (class "Default")
      (node (ref "IC3") (pin "10") (pinfunction "PGND2'_10") (pintype "power_in"))
      (node (ref "IC3") (pin "9") (pinfunction "PGND2_9") (pintype "power_in"))
      (node (ref "J22") (pin "2") (pinfunction "2_2") (pintype "passive"))
    )
    (net (code "47") (name "Net-(IC3-STBY)") (class "Default")
      (node (ref "IC3") (pin "19") (pinfunction "STBY_19") (pintype "input"))
      (node (ref "R6") (pin "2") (pinfunction "2_2") (pintype "passive"))
    )
    (net (code "48") (name "Net-(J4-Pad1)") (class "Default")
      (node (ref "J4") (pin "1") (pinfunction "1_1") (pintype "passive"))
      (node (ref "K1") (pin "P") (pinfunction "P_P") (pintype "passive"))
    )
    (net (code "49") (name "Net-(J7-Pad1)") (class "Default")
      (node (ref "J7") (pin "1") (pinfunction "1_1") (pintype "passive"))
      (node (ref "K2") (pin "P") (pinfunction "P_P") (pintype "passive"))
    )
    (net (code "50") (name "Net-(J9-Pad1)") (class "Default")
      (node (ref "J9") (pin "1") (pinfunction "1_1") (pintype "passive"))
      (node (ref "K3") (pin "P") (pinfunction "P_P") (pintype "passive"))
    )
    (net (code "51") (name "Net-(J10-Pad1)") (class "Default")
      (node (ref "J10") (pin "1") (pinfunction "1_1") (pintype "passive"))
      (node (ref "K4") (pin "P") (pinfunction "P_P") (pintype "passive"))
    )
    (net (code "52") (name "Net-(JP1-Pad2)") (class "Default")
      (node (ref "JP1") (pin "2") (pinfunction "2_2") (pintype "passive"))
      (node (ref "SJ1") (pin "2") (pinfunction "2_2") (pintype "passive"))
      (node (ref "SJ2") (pin "2") (pinfunction "2_2") (pintype "passive"))
    )
    (net (code "53") (name "Net-(JP2-Pad2)") (class "Default")
      (node (ref "JP2") (pin "2") (pinfunction "2_2") (pintype "passive"))
      (node (ref "SJ3") (pin "2") (pinfunction "2_2") (pintype "passive"))
      (node (ref "SJ4") (pin "2") (pinfunction "2_2") (pintype "passive"))
    )
    (net (code "54") (name "Net-(JP3-Pad2)") (class "Default")
      (node (ref "JP3") (pin "2") (pinfunction "2_2") (pintype "passive"))
      (node (ref "SJ5") (pin "2") (pinfunction "2_2") (pintype "passive"))
      (node (ref "SJ6") (pin "2") (pinfunction "2_2") (pintype "passive"))
    )
    (net (code "55") (name "Net-(JP4-Pad2)") (class "Default")
      (node (ref "JP4") (pin "2") (pinfunction "2_2") (pintype "passive"))
      (node (ref "SJ7") (pin "2") (pinfunction "2_2") (pintype "passive"))
      (node (ref "SJ8") (pin "2") (pinfunction "2_2") (pintype "passive"))
    )
    (net (code "56") (name "Net-(U$1-RX)") (class "Default")
      (node (ref "SJ11") (pin "1") (pinfunction "1_1") (pintype "passive"))
      (node (ref "SJ12") (pin "1") (pinfunction "1_1") (pintype "passive"))
      (node (ref "U$1") (pin "10") (pinfunction "RX_10") (pintype "bidirectional"))
    )
    (net (code "57") (name "Net-(U$1-TX)") (class "Default")
      (node (ref "SJ10") (pin "1") (pinfunction "1_1") (pintype "passive"))
      (node (ref "SJ9") (pin "1") (pinfunction "1_1") (pintype "passive"))
      (node (ref "U$1") (pin "8") (pinfunction "TX_8") (pintype "bidirectional"))
    )
    (net (code "58") (name "Net-(U$3-IN+)") (class "Default")
      (node (ref "C1") (pin "1") (pinfunction "1_1") (pintype "passive"))
      (node (ref "C2") (pin "2") (pinfunction "2_2") (pintype "passive"))
      (node (ref "J6") (pin "2") (pinfunction "2_2") (pintype "passive"))
      (node (ref "U$3") (pin "8") (pinfunction "IN+_8") (pintype "bidirectional"))
    )
    (net (code "59") (name "Net-(U$3-IN-)") (class "Default")
      (node (ref "C1") (pin "2") (pinfunction "2_2") (pintype "passive"))
      (node (ref "C3") (pin "1") (pinfunction "1_1") (pintype "passive"))
      (node (ref "J6") (pin "1") (pinfunction "1_1") (pintype "passive"))
      (node (ref "R1") (pin "2") (pinfunction "2_2") (pintype "passive"))
      (node (ref "U$3") (pin "1") (pinfunction "IN-_1") (pintype "bidirectional"))
    )
    (net (code "60") (name "Net-(U$4A-B)") (class "Default")
      (node (ref "R8") (pin "1") (pinfunction "1_1") (pintype "passive"))
      (node (ref "U$4") (pin "P$5") (pinfunction "B_P$5") (pintype "passive"))
    )
    (net (code "61") (name "Net-(U$4A-C)") (class "Default")
      (node (ref "K2") (pin "1") (pinfunction "1_1") (pintype "passive"))
      (node (ref "U$4") (pin "P$4") (pinfunction "C_P$4") (pintype "passive"))
    )
    (net (code "62") (name "Net-(U$4B-B)") (class "Default")
      (node (ref "R7") (pin "1") (pinfunction "1_1") (pintype "passive"))
      (node (ref "U$4") (pin "P$2") (pinfunction "B_P$2") (pintype "passive"))
    )
    (net (code "63") (name "Net-(U$4B-C)") (class "Default")
      (node (ref "K1") (pin "1") (pinfunction "1_1") (pintype "passive"))
      (node (ref "U$4") (pin "P$1") (pinfunction "C_P$1") (pintype "passive"))
    )
    (net (code "64") (name "Net-(U$5A-B)") (class "Default")
      (node (ref "R9") (pin "1") (pinfunction "1_1") (pintype "passive"))
      (node (ref "U$5") (pin "P$5") (pinfunction "B_P$5") (pintype "passive"))
    )
    (net (code "65") (name "Net-(U$5A-C)") (class "Default")
      (node (ref "K3") (pin "1") (pinfunction "1_1") (pintype "passive"))
      (node (ref "U$5") (pin "P$4") (pinfunction "C_P$4") (pintype "passive"))
    )
    (net (code "66") (name "Net-(U$5B-B)") (class "Default")
      (node (ref "R10") (pin "1") (pinfunction "1_1") (pintype "passive"))
      (node (ref "U$5") (pin "P$2") (pinfunction "B_P$2") (pintype "passive"))
    )
    (net (code "67") (name "Net-(U$5B-C)") (class "Default")
      (node (ref "K4") (pin "1") (pinfunction "1_1") (pintype "passive"))
      (node (ref "U$5") (pin "P$1") (pinfunction "C_P$1") (pintype "passive"))
    )
    (net (code "68") (name "Net-(U$6-IN+)") (class "Default")
      (node (ref "C5") (pin "1") (pinfunction "1_1") (pintype "passive"))
      (node (ref "C6") (pin "2") (pinfunction "2_2") (pintype "passive"))
      (node (ref "J3") (pin "2") (pinfunction "2_2") (pintype "passive"))
      (node (ref "U$6") (pin "8") (pinfunction "IN+_8") (pintype "bidirectional"))
    )
    (net (code "69") (name "Net-(U$6-IN-)") (class "Default")
      (node (ref "C5") (pin "2") (pinfunction "2_2") (pintype "passive"))
      (node (ref "C7") (pin "1") (pinfunction "1_1") (pintype "passive"))
      (node (ref "J3") (pin "1") (pinfunction "1_1") (pintype "passive"))
      (node (ref "R2") (pin "2") (pinfunction "2_2") (pintype "passive"))
      (node (ref "U$6") (pin "1") (pinfunction "IN-_1") (pintype "bidirectional"))
    )
    (net (code "70") (name "Net-(U$7-IN+)") (class "Default")
      (node (ref "C10") (pin "2") (pinfunction "2_2") (pintype "passive"))
      (node (ref "C9") (pin "1") (pinfunction "1_1") (pintype "passive"))
      (node (ref "J5") (pin "2") (pinfunction "2_2") (pintype "passive"))
      (node (ref "U$7") (pin "8") (pinfunction "IN+_8") (pintype "bidirectional"))
    )
    (net (code "71") (name "Net-(U$7-IN-)") (class "Default")
      (node (ref "C11") (pin "1") (pinfunction "1_1") (pintype "passive"))
      (node (ref "C9") (pin "2") (pinfunction "2_2") (pintype "passive"))
      (node (ref "J5") (pin "1") (pinfunction "1_1") (pintype "passive"))
      (node (ref "R3") (pin "2") (pinfunction "2_2") (pintype "passive"))
      (node (ref "U$7") (pin "1") (pinfunction "IN-_1") (pintype "bidirectional"))
    )
    (net (code "72") (name "PRESSURE1") (class "Default")
      (node (ref "J12") (pin "1") (pinfunction "1_1") (pintype "passive"))
      (node (ref "U$2") (pin "20") (pinfunction "PA4_20") (pintype "bidirectional"))
    )
    (net (code "73") (name "PRESSURE2") (class "Default")
      (node (ref "J14") (pin "1") (pinfunction "1_1") (pintype "passive"))
      (node (ref "U$2") (pin "21") (pinfunction "PA5_21") (pintype "bidirectional"))
    )
    (net (code "74") (name "RX") (class "Default")
      (node (ref "SJ11") (pin "2") (pinfunction "2_2") (pintype "passive"))
      (node (ref "SJ9") (pin "2") (pinfunction "2_2") (pintype "passive"))
      (node (ref "U$2") (pin "24") (pinfunction "PC4_24") (pintype "bidirectional"))
    )
    (net (code "75") (name "SERVO1") (class "Default")
      (node (ref "JP1") (pin "1") (pinfunction "1_1") (pintype "passive"))
      (node (ref "U$2") (pin "37") (pinfunction "PC6_37") (pintype "bidirectional"))
    )
    (net (code "76") (name "SERVO2") (class "Default")
      (node (ref "JP2") (pin "1") (pinfunction "1_1") (pintype "passive"))
      (node (ref "U$2") (pin "38") (pinfunction "PC7_38") (pintype "bidirectional"))
    )
    (net (code "77") (name "SERVO3") (class "Default")
      (node (ref "JP3") (pin "1") (pinfunction "1_1") (pintype "passive"))
      (node (ref "U$2") (pin "39") (pinfunction "PC8_39") (pintype "bidirectional"))
    )
    (net (code "78") (name "SERVO4") (class "Default")
      (node (ref "JP4") (pin "1") (pinfunction "1_1") (pintype "passive"))
      (node (ref "U$2") (pin "40") (pinfunction "PC9_40") (pintype "bidirectional"))
    )
    (net (code "79") (name "SWDCLK") (class "Default")
      (node (ref "SV1") (pin "2") (pinfunction "2_2") (pintype "passive"))
      (node (ref "U$2") (pin "49") (pinfunction "PA14_49") (pintype "bidirectional"))
    )
    (net (code "80") (name "SWDIO") (class "Default")
      (node (ref "SV1") (pin "4") (pinfunction "4_4") (pintype "passive"))
      (node (ref "U$2") (pin "46") (pinfunction "PA13_46") (pintype "bidirectional"))
    )
    (net (code "81") (name "SWIM") (class "Default")
      (node (ref "SV1") (pin "3") (pinfunction "3_3") (pintype "passive"))
      (node (ref "U$2") (pin "61") (pinfunction "PB8_61") (pintype "bidirectional"))
    )
    (net (code "82") (name "TEMP1") (class "Default")
      (node (ref "U$2") (pin "15") (pinfunction "PA1_15") (pintype "bidirectional"))
      (node (ref "U$3") (pin "5") (pinfunction "SENSE_5") (pintype "bidirectional"))
      (node (ref "U$3") (pin "6") (pinfunction "OUT_6") (pintype "bidirectional"))
    )
    (net (code "83") (name "TEMP2") (class "Default")
      (node (ref "U$2") (pin "16") (pinfunction "PA2_16") (pintype "bidirectional"))
      (node (ref "U$6") (pin "5") (pinfunction "SENSE_5") (pintype "bidirectional"))
      (node (ref "U$6") (pin "6") (pinfunction "OUT_6") (pintype "bidirectional"))
    )
    (net (code "84") (name "TEMP3") (class "Default")
      (node (ref "U$2") (pin "17") (pinfunction "PA3_17") (pintype "bidirectional"))
      (node (ref "U$7") (pin "5") (pinfunction "SENSE_5") (pintype "bidirectional"))
      (node (ref "U$7") (pin "6") (pinfunction "OUT_6") (pintype "bidirectional"))
    )
    (net (code "85") (name "TX") (class "Default")
      (node (ref "SJ10") (pin "2") (pinfunction "2_2") (pintype "passive"))
      (node (ref "SJ12") (pin "2") (pinfunction "2_2") (pintype "passive"))
      (node (ref "U$2") (pin "25") (pinfunction "PC5_25") (pintype "bidirectional"))
    )
    (net (code "86") (name "V+") (class "Default")
      (node (ref "J8") (pin "2") (pinfunction "2_2") (pintype "passive"))
      (node (ref "K2") (pin "S") (pinfunction "S_S") (pintype "passive"))
      (node (ref "K3") (pin "S") (pinfunction "S_S") (pintype "passive"))
      (node (ref "K4") (pin "S") (pinfunction "S_S") (pintype "passive"))
    )
    (net (code "87") (name "V-") (class "Default")
      (node (ref "J10") (pin "2") (pinfunction "2_2") (pintype "passive"))
      (node (ref "J7") (pin "2") (pinfunction "2_2") (pintype "passive"))
      (node (ref "J8") (pin "1") (pinfunction "1_1") (pintype "passive"))
      (node (ref "J9") (pin "2") (pinfunction "2_2") (pintype "passive"))
    )
    (net (code "88") (name "unconnected-(K1-PadO)") (class "Default")
      (node (ref "K1") (pin "O") (pinfunction "O_O") (pintype "passive"))
    )
    (net (code "89") (name "unconnected-(K2-PadO)") (class "Default")
      (node (ref "K2") (pin "O") (pinfunction "O_O") (pintype "passive"))
    )
    (net (code "90") (name "unconnected-(K3-PadO)") (class "Default")
      (node (ref "K3") (pin "O") (pinfunction "O_O") (pintype "passive"))
    )
    (net (code "91") (name "unconnected-(K4-PadO)") (class "Default")
      (node (ref "K4") (pin "O") (pinfunction "O_O") (pintype "passive"))
    )
    (net (code "92") (name "unconnected-(U$1-3.3-Pad1)") (class "Default")
      (node (ref "U$1") (pin "1") (pinfunction "3.3_1") (pintype "bidirectional"))
    )
    (net (code "93") (name "unconnected-(U$1-3.3-Pad17)") (class "Default")
      (node (ref "U$1") (pin "17") (pinfunction "3.3_17") (pintype "bidirectional"))
    )
    (net (code "94") (name "unconnected-(U$1-GND-Pad25)") (class "Default")
      (node (ref "U$1") (pin "25") (pinfunction "GND_25") (pintype "bidirectional"))
    )
    (net (code "95") (name "unconnected-(U$1-GND-Pad30)") (class "Default")
      (node (ref "U$1") (pin "30") (pinfunction "GND_30") (pintype "bidirectional"))
    )
    (net (code "96") (name "unconnected-(U$1-GPIO2-Pad3)") (class "Default")
      (node (ref "U$1") (pin "3") (pinfunction "GPIO2_3") (pintype "bidirectional"))
    )
    (net (code "97") (name "unconnected-(U$1-GPIO3-Pad5)") (class "Default")
      (node (ref "U$1") (pin "5") (pinfunction "GPIO3_5") (pintype "bidirectional"))
    )
    (net (code "98") (name "unconnected-(U$1-GPIO4-Pad7)") (class "Default")
      (node (ref "U$1") (pin "7") (pinfunction "GPIO4_7") (pintype "bidirectional"))
    )
    (net (code "99") (name "unconnected-(U$1-GPIO5-Pad29)") (class "Default")
      (node (ref "U$1") (pin "29") (pinfunction "GPIO5_29") (pintype "bidirectional"))
    )
    (net (code "100") (name "unconnected-(U$1-GPIO6-Pad31)") (class "Default")
      (node (ref "U$1") (pin "31") (pinfunction "GPIO6_31") (pintype "bidirectional"))
    )
    (net (code "101") (name "unconnected-(U$1-GPIO7-Pad26)") (class "Default")
      (node (ref "U$1") (pin "26") (pinfunction "GPIO7_26") (pintype "bidirectional"))
    )
    (net (code "102") (name "unconnected-(U$1-GPIO8-Pad24)") (class "Default")
      (node (ref "U$1") (pin "24") (pinfunction "GPIO8_24") (pintype "bidirectional"))
    )
    (net (code "103") (name "unconnected-(U$1-GPIO9-Pad21)") (class "Default")
      (node (ref "U$1") (pin "21") (pinfunction "GPIO9_21") (pintype "bidirectional"))
    )
    (net (code "104") (name "unconnected-(U$1-GPIO10-Pad19)") (class "Default")
      (node (ref "U$1") (pin "19") (pinfunction "GPIO10_19") (pintype "bidirectional"))
    )
    (net (code "105") (name "unconnected-(U$1-GPIO11-Pad23)") (class "Default")
      (node (ref "U$1") (pin "23") (pinfunction "GPIO11_23") (pintype "bidirectional"))
    )
    (net (code "106") (name "unconnected-(U$1-GPIO12-Pad32)") (class "Default")
      (node (ref "U$1") (pin "32") (pinfunction "GPIO12_32") (pintype "bidirectional"))
    )
    (net (code "107") (name "unconnected-(U$1-GPIO13-Pad33)") (class "Default")
      (node (ref "U$1") (pin "33") (pinfunction "GPIO13_33") (pintype "bidirectional"))
    )
    (net (code "108") (name "unconnected-(U$1-GPIO16-Pad36)") (class "Default")
      (node (ref "U$1") (pin "36") (pinfunction "GPIO16_36") (pintype "bidirectional"))
    )
    (net (code "109") (name "unconnected-(U$1-GPIO17-Pad11)") (class "Default")
      (node (ref "U$1") (pin "11") (pinfunction "GPIO17_11") (pintype "bidirectional"))
    )
    (net (code "110") (name "unconnected-(U$1-GPIO18-Pad12)") (class "Default")
      (node (ref "U$1") (pin "12") (pinfunction "GPIO18_12") (pintype "bidirectional"))
    )
    (net (code "111") (name "unconnected-(U$1-GPIO19-Pad35)") (class "Default")
      (node (ref "U$1") (pin "35") (pinfunction "GPIO19_35") (pintype "bidirectional"))
    )
    (net (code "112") (name "unconnected-(U$1-GPIO20-Pad38)") (class "Default")
      (node (ref "U$1") (pin "38") (pinfunction "GPIO20_38") (pintype "bidirectional"))
    )
    (net (code "113") (name "unconnected-(U$1-GPIO21-Pad40)") (class "Default")
      (node (ref "U$1") (pin "40") (pinfunction "GPIO21_40") (pintype "bidirectional"))
    )
    (net (code "114") (name "unconnected-(U$1-GPIO22-Pad15)") (class "Default")
      (node (ref "U$1") (pin "15") (pinfunction "GPIO22_15") (pintype "bidirectional"))
    )
    (net (code "115") (name "unconnected-(U$1-GPIO23-Pad16)") (class "Default")
      (node (ref "U$1") (pin "16") (pinfunction "GPIO23_16") (pintype "bidirectional"))
    )
    (net (code "116") (name "unconnected-(U$1-GPIO24-Pad18)") (class "Default")
      (node (ref "U$1") (pin "18") (pinfunction "GPIO24_18") (pintype "bidirectional"))
    )
    (net (code "117") (name "unconnected-(U$1-GPIO25-Pad22)") (class "Default")
      (node (ref "U$1") (pin "22") (pinfunction "GPIO25_22") (pintype "bidirectional"))
    )
    (net (code "118") (name "unconnected-(U$1-GPIO26-Pad37)") (class "Default")
      (node (ref "U$1") (pin "37") (pinfunction "GPIO26_37") (pintype "bidirectional"))
    )
    (net (code "119") (name "unconnected-(U$1-GPIO27-Pad13)") (class "Default")
      (node (ref "U$1") (pin "13") (pinfunction "GPIO27_13") (pintype "bidirectional"))
    )
    (net (code "120") (name "unconnected-(U$1-RES-Pad27)") (class "Default")
      (node (ref "U$1") (pin "27") (pinfunction "RES_27") (pintype "bidirectional"))
    )
    (net (code "121") (name "unconnected-(U$1-RES-Pad28)") (class "Default")
      (node (ref "U$1") (pin "28") (pinfunction "RES_28") (pintype "bidirectional"))
    )
    (net (code "122") (name "unconnected-(U$2-BOOT0-Pad60)") (class "Default")
      (node (ref "U$2") (pin "60") (pinfunction "BOOT0_60") (pintype "bidirectional"))
    )
    (net (code "123") (name "unconnected-(U$2-PA12-Pad45)") (class "Default")
      (node (ref "U$2") (pin "45") (pinfunction "PA12_45") (pintype "bidirectional"))
    )
    (net (code "124") (name "unconnected-(U$2-PA15-Pad50)") (class "Default")
      (node (ref "U$2") (pin "50") (pinfunction "PA15_50") (pintype "bidirectional"))
    )
    (net (code "125") (name "unconnected-(U$2-PB1-Pad27)") (class "Default")
      (node (ref "U$2") (pin "27") (pinfunction "PB1_27") (pintype "bidirectional"))
    )
    (net (code "126") (name "unconnected-(U$2-PB9-Pad62)") (class "Default")
      (node (ref "U$2") (pin "62") (pinfunction "PB9_62") (pintype "bidirectional"))
    )
    (net (code "127") (name "unconnected-(U$2-PB13-Pad34)") (class "Default")
      (node (ref "U$2") (pin "34") (pinfunction "PB13_34") (pintype "bidirectional"))
    )
    (net (code "128") (name "unconnected-(U$2-PB14-Pad35)") (class "Default")
      (node (ref "U$2") (pin "35") (pinfunction "PB14_35") (pintype "bidirectional"))
    )
    (net (code "129") (name "unconnected-(U$2-PB15-Pad36)") (class "Default")
      (node (ref "U$2") (pin "36") (pinfunction "PB15_36") (pintype "bidirectional"))
    )
    (net (code "130") (name "unconnected-(U$2-PC13-Pad2)") (class "Default")
      (node (ref "U$2") (pin "2") (pinfunction "PC13_2") (pintype "bidirectional"))
    )
    (net (code "131") (name "unconnected-(U$2-PC14-OSC32_IN-Pad3)") (class "Default")
      (node (ref "U$2") (pin "3") (pinfunction "PC14-OSC32_IN_3") (pintype "bidirectional"))
    )
    (net (code "132") (name "unconnected-(U$2-PC15-OSC32_OUT-Pad4)") (class "Default")
      (node (ref "U$2") (pin "4") (pinfunction "PC15-OSC32_OUT_4") (pintype "bidirectional"))
    )
    (net (code "133") (name "unconnected-(U$2-PF0-OSC_IN-Pad5)") (class "Default")
      (node (ref "U$2") (pin "5") (pinfunction "PF0-OSC_IN_5") (pintype "bidirectional"))
    )
    (net (code "134") (name "unconnected-(U$2-PF1-OSC_OUT-Pad6)") (class "Default")
      (node (ref "U$2") (pin "6") (pinfunction "PF1-OSC_OUT_6") (pintype "bidirectional"))
    )
    (net (code "135") (name "unconnected-(U$2-VBAT-Pad1)") (class "Default")
      (node (ref "U$2") (pin "1") (pinfunction "VBAT_1") (pintype "bidirectional"))
    )
    (net (code "136") (name "~{RELAY1}") (class "Default")
      (node (ref "R7") (pin "2") (pinfunction "2_2") (pintype "passive"))
      (node (ref "U$2") (pin "51") (pinfunction "PC10_51") (pintype "bidirectional"))
    )
    (net (code "137") (name "~{RELAY2}") (class "Default")
      (node (ref "R8") (pin "2") (pinfunction "2_2") (pintype "passive"))
      (node (ref "U$2") (pin "52") (pinfunction "PC11_52") (pintype "bidirectional"))
    )
    (net (code "138") (name "~{RELAY3}") (class "Default")
      (node (ref "R9") (pin "2") (pinfunction "2_2") (pintype "passive"))
      (node (ref "U$2") (pin "53") (pinfunction "PC12_53") (pintype "bidirectional"))
    )
    (net (code "139") (name "~{RELAY4}") (class "Default")
      (node (ref "R10") (pin "2") (pinfunction "2_2") (pintype "passive"))
      (node (ref "U$2") (pin "54") (pinfunction "PD2_54") (pintype "bidirectional"))
    )
  )
)
